# untitled.net
KiCad netlist of a schematic drawn in EAGLE
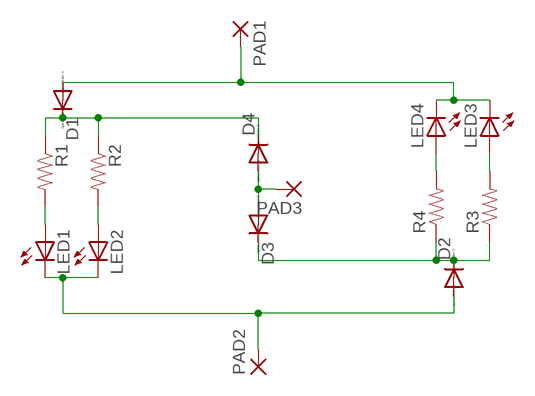
[diagram p0: schematic, sheet 1]

(export (version "E")
  (design (tool "Eeschema 10.0.6"))
  (components
    (comp (ref "D1")
      (value "DIODE-DO-214AC")
      (footprint "eagle-import:DO-214AC")
      (libsource (lib "eagle-import") (part "DIODE-DO-214AC"))
    )
    (comp (ref "D2")
      (value "DIODE-DO-214AC")
      (footprint "eagle-import:DO-214AC")
      (libsource (lib "eagle-import") (part "DIODE-DO-214AC"))
    )
    (comp (ref "D3")
      (value "DIODE-DO-214AC")
      (footprint "eagle-import:DO-214AC")
      (libsource (lib "eagle-import") (part "DIODE-DO-214AC"))
    )
    (comp (ref "D4")
      (value "DIODE-DO-214AC")
      (footprint "eagle-import:DO-214AC")
      (libsource (lib "eagle-import") (part "DIODE-DO-214AC"))
    )
    (comp (ref "LED1")
      (value "LEDCHIP-LED0805")
      (footprint "eagle-import:CHIP-LED0805")
      (libsource (lib "eagle-import") (part "LEDCHIP-LED0805"))
    )
    (comp (ref "LED2")
      (value "LEDCHIP-LED0805")
      (footprint "eagle-import:CHIP-LED0805")
      (libsource (lib "eagle-import") (part "LEDCHIP-LED0805"))
    )
    (comp (ref "LED3")
      (value "LEDCHIP-LED0805")
      (footprint "eagle-import:CHIP-LED0805")
      (libsource (lib "eagle-import") (part "LEDCHIP-LED0805"))
    )
    (comp (ref "LED4")
      (value "LEDCHIP-LED0805")
      (footprint "eagle-import:CHIP-LED0805")
      (libsource (lib "eagle-import") (part "LEDCHIP-LED0805"))
    )
    (comp (ref "PAD1")
      (value "2,15/1,0")
      (footprint "eagle-import:2,15_1,0")
      (libsource (lib "eagle-import") (part "2,15/1,0"))
    )
    (comp (ref "PAD2")
      (value "2,15/1,0")
      (footprint "eagle-import:2,15_1,0")
      (libsource (lib "eagle-import") (part "2,15/1,0"))
    )
    (comp (ref "PAD3")
      (value "2,15/1,0")
      (footprint "eagle-import:2,15_1,0")
      (libsource (lib "eagle-import") (part "2,15/1,0"))
    )
    (comp (ref "R1")
      (value "RESISTOR0805-RES")
      (footprint "eagle-import:0805")
      (libsource (lib "eagle-import") (part "RESISTOR0805-RES"))
    )
    (comp (ref "R2")
      (value "RESISTOR0805-RES")
      (footprint "eagle-import:0805")
      (libsource (lib "eagle-import") (part "RESISTOR0805-RES"))
    )
    (comp (ref "R3")
      (value "RESISTOR0805-RES")
      (footprint "eagle-import:0805")
      (libsource (lib "eagle-import") (part "RESISTOR0805-RES"))
    )
    (comp (ref "R4")
      (value "RESISTOR0805-RES")
      (footprint "eagle-import:0805")
      (libsource (lib "eagle-import") (part "RESISTOR0805-RES"))
    )
  )
  (nets
    (net (code "1") (name "Net-(D1-PadC)") (class "Default")
      (node (ref "D1") (pin "C") (pinfunction "C_C") (pintype "passive"))
      (node (ref "D4") (pin "C") (pinfunction "C_C") (pintype "passive"))
      (node (ref "R1") (pin "1") (pinfunction "1_1") (pintype "passive"))
      (node (ref "R2") (pin "1") (pinfunction "1_1") (pintype "passive"))
    )
    (net (code "2") (name "Net-(D2-PadC)") (class "Default")
      (node (ref "D2") (pin "C") (pinfunction "C_C") (pintype "passive"))
      (node (ref "D3") (pin "C") (pinfunction "C_C") (pintype "passive"))
      (node (ref "R3") (pin "1") (pinfunction "1_1") (pintype "passive"))
      (node (ref "R4") (pin "1") (pinfunction "1_1") (pintype "passive"))
    )
    (net (code "3") (name "Net-(LED1-PadA)") (class "Default")
      (node (ref "LED1") (pin "A") (pinfunction "A_A") (pintype "passive"))
      (node (ref "R1") (pin "2") (pinfunction "2_2") (pintype "passive"))
    )
    (net (code "4") (name "Net-(LED2-PadA)") (class "Default")
      (node (ref "LED2") (pin "A") (pinfunction "A_A") (pintype "passive"))
      (node (ref "R2") (pin "2") (pinfunction "2_2") (pintype "passive"))
    )
    (net (code "5") (name "Net-(LED3-PadA)") (class "Default")
      (node (ref "LED3") (pin "A") (pinfunction "A_A") (pintype "passive"))
      (node (ref "R3") (pin "2") (pinfunction "2_2") (pintype "passive"))
    )
    (net (code "6") (name "Net-(LED4-PadA)") (class "Default")
      (node (ref "LED4") (pin "A") (pinfunction "A_A") (pintype "passive"))
      (node (ref "R4") (pin "2") (pinfunction "2_2") (pintype "passive"))
    )
    (net (code "7") (name "Net-(PAD1-P)") (class "Default")
      (node (ref "D1") (pin "A") (pinfunction "A_A") (pintype "passive"))
      (node (ref "LED3") (pin "C") (pinfunction "C_C") (pintype "passive"))
      (node (ref "LED4") (pin "C") (pinfunction "C_C") (pintype "passive"))
      (node (ref "PAD1") (pin "1") (pinfunction "P_1") (pintype "passive"))
    )
    (net (code "8") (name "Net-(PAD2-P)") (class "Default")
      (node (ref "D2") (pin "A") (pinfunction "A_A") (pintype "passive"))
      (node (ref "LED1") (pin "C") (pinfunction "C_C") (pintype "passive"))
      (node (ref "LED2") (pin "C") (pinfunction "C_C") (pintype "passive"))
      (node (ref "PAD2") (pin "1") (pinfunction "P_1") (pintype "passive"))
    )
    (net (code "9") (name "Net-(PAD3-P)") (class "Default")
      (node (ref "D3") (pin "A") (pinfunction "A_A") (pintype "passive"))
      (node (ref "D4") (pin "A") (pinfunction "A_A") (pintype "passive"))
      (node (ref "PAD3") (pin "1") (pinfunction "P_1") (pintype "passive"))
    )
  )
)
